# ID2.net
KiCad netlist of a schematic drawn in Altium Designer
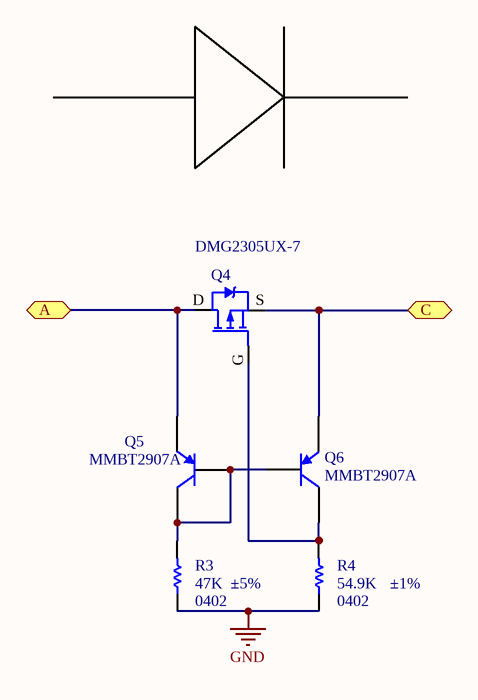
[diagram p0: ID2.SchDoc]

(export (version "E")
  (design (tool "Eeschema 10.0.6"))
  (components
    (comp (ref "Q4")
      (value "DMG2305UX")
      (footprint "DMG2305UX-7")
      (description "MOSFET P-CH 20V 4.2A SOT23")
      (fields
        (field (name "MANUFACTURER") "Diodes Incorporated")
        (field (name "MANUFACTURER PART NUMBER") "DMG2305UX-7")
        (field (name "CREATOR") "osman")
      )
      (libsource (lib "OLogic-Trans-Drivers") (part "DMG2305UX"))
    )
    (comp (ref "Q5")
      (value "MMBT2907A")
      (footprint "SOT23")
      (description "PNP General Purpose Amplifier")
      (fields (field (name "MANUFACTURER") "Fairchild Semiconductor"))
      (libsource (lib "OLogic-Trans-Drivers") (part "MMBT2907A"))
    )
    (comp (ref "Q6")
      (value "MMBT2907A")
      (footprint "SOT23")
      (description "PNP General Purpose Amplifier")
      (fields (field (name "MANUFACTURER") "Fairchild Semiconductor"))
      (libsource (lib "OLogic-Trans-Drivers") (part "MMBT2907A"))
    )
    (comp (ref "R3")
      (value "47K")
      (footprint "RESC0402(1005)_N")
      (description "47K 0402")
      (fields
        (field (name "MANUFACTURER") "Panasonic Electronic Components")
        (field (name "MANUFACTURER PART NUMBER") "ERJ-2GEJ473X")
        (field (name "TOLERANCE") "±5%")
        (field (name "SUPPLIER DEVICE PACKAGE") "0402")
      )
      (libsource (lib "OLogic-Passive") (part "RES 47K OHM 5% 1/10W 0402"))
    )
    (comp (ref "R4")
      (value "54.9K")
      (footprint "RESC0402(1005)_N")
      (description "54.9K 1% 0402")
      (fields
        (field (name "MANUFACTURER") "Panasonic Electronic Components")
        (field (name "MANUFACTURER PART NUMBER") "ERJ-2RKF5492X")
        (field (name "TOLERANCE") "±1%")
        (field (name "SUPPLIER DEVICE PACKAGE") "0402")
      )
      (libsource (lib "OLogic-Passive") (part "RES 54.9K OHM 1% 1/10W 0402"))
    )
  )
  (nets
    (net (code "1") (name "/A") (class "Default")
      (node (ref "Q4") (pin "D") (pinfunction "D_D") (pintype "passive"))
      (node (ref "Q5") (pin "2") (pinfunction "E_2") (pintype "passive"))
    )
    (net (code "2") (name "/C") (class "Default")
      (node (ref "Q4") (pin "S") (pinfunction "S_S") (pintype "passive"))
      (node (ref "Q6") (pin "2") (pinfunction "E_2") (pintype "passive"))
    )
    (net (code "3") (name "GND") (class "Default")
      (node (ref "R3") (pin "1") (pinfunction "1_1") (pintype "passive"))
      (node (ref "R4") (pin "1") (pinfunction "1_1") (pintype "passive"))
    )
    (net (code "4") (name "Net-(Q5-B)") (class "Default")
      (node (ref "Q5") (pin "1") (pinfunction "B_1") (pintype "passive"))
      (node (ref "Q5") (pin "3") (pinfunction "C_3") (pintype "passive"))
      (node (ref "Q6") (pin "1") (pinfunction "B_1") (pintype "passive"))
      (node (ref "R3") (pin "2") (pinfunction "2_2") (pintype "passive"))
    )
    (net (code "5") (name "Net-(Q6-C)") (class "Default")
      (node (ref "Q4") (pin "G") (pinfunction "G_G") (pintype "passive"))
      (node (ref "Q6") (pin "3") (pinfunction "C_3") (pintype "passive"))
      (node (ref "R4") (pin "2") (pinfunction "2_2") (pintype "passive"))
    )
  )
)
